# astablemultivibrator.net
KiCad netlist of a schematic drawn in EAGLE
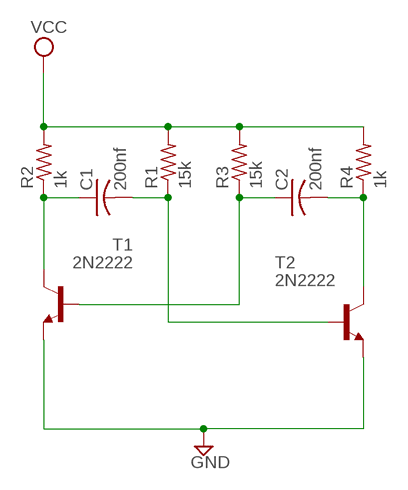
[diagram p0: schematic, sheet 1]

(export (version "E")
  (design (tool "Eeschema 10.0.6"))
  (components
    (comp (ref "C1")
      (value "200nf")
      (footprint "eagle-import:C025-030X050")
      (libsource (lib "eagle-import") (part "C-US025-030X050"))
    )
    (comp (ref "C2")
      (value "200nf")
      (footprint "eagle-import:C025-030X050")
      (libsource (lib "eagle-import") (part "C-US025-030X050"))
    )
    (comp (ref "R1")
      (value "15k")
      (footprint "eagle-import:0309_12")
      (libsource (lib "eagle-import") (part "R-US_0309/12"))
    )
    (comp (ref "R2")
      (value "1k")
      (footprint "eagle-import:0309_12")
      (libsource (lib "eagle-import") (part "R-US_0309/12"))
    )
    (comp (ref "R3")
      (value "15k")
      (footprint "eagle-import:0309_12")
      (libsource (lib "eagle-import") (part "R-US_0309/12"))
    )
    (comp (ref "R4")
      (value "1k")
      (footprint "eagle-import:0309_12")
      (libsource (lib "eagle-import") (part "R-US_0309/12"))
    )
    (comp (ref "T1")
      (value "2N2222")
      (footprint "eagle-import:TO92-EBC-OVAL")
      (libsource (lib "eagle-import") (part "2N2222"))
    )
    (comp (ref "T2")
      (value "2N2222")
      (footprint "eagle-import:TO92-EBC-OVAL")
      (libsource (lib "eagle-import") (part "2N2222"))
    )
  )
  (nets
    (net (code "1") (name "GND") (class "Default")
      (node (ref "T1") (pin "E") (pinfunction "E_E") (pintype "passive"))
      (node (ref "T2") (pin "E") (pinfunction "E_E") (pintype "passive"))
    )
    (net (code "2") (name "Net-(C1-Pad1)") (class "Default")
      (node (ref "C1") (pin "1") (pinfunction "1_1") (pintype "passive"))
      (node (ref "R2") (pin "1") (pinfunction "1_1") (pintype "passive"))
      (node (ref "T1") (pin "C") (pinfunction "C_C") (pintype "passive"))
    )
    (net (code "3") (name "Net-(C1-Pad2)") (class "Default")
      (node (ref "C1") (pin "2") (pinfunction "2_2") (pintype "passive"))
      (node (ref "R1") (pin "1") (pinfunction "1_1") (pintype "passive"))
      (node (ref "T2") (pin "B") (pinfunction "B_B") (pintype "passive"))
    )
    (net (code "4") (name "Net-(C2-Pad1)") (class "Default")
      (node (ref "C2") (pin "1") (pinfunction "1_1") (pintype "passive"))
      (node (ref "R3") (pin "1") (pinfunction "1_1") (pintype "passive"))
      (node (ref "T1") (pin "B") (pinfunction "B_B") (pintype "passive"))
    )
    (net (code "5") (name "Net-(C2-Pad2)") (class "Default")
      (node (ref "C2") (pin "2") (pinfunction "2_2") (pintype "passive"))
      (node (ref "R4") (pin "1") (pinfunction "1_1") (pintype "passive"))
      (node (ref "T2") (pin "C") (pinfunction "C_C") (pintype "passive"))
    )
    (net (code "6") (name "VCC") (class "Default")
      (node (ref "R1") (pin "2") (pinfunction "2_2") (pintype "passive"))
      (node (ref "R2") (pin "2") (pinfunction "2_2") (pintype "passive"))
      (node (ref "R3") (pin "2") (pinfunction "2_2") (pintype "passive"))
      (node (ref "R4") (pin "2") (pinfunction "2_2") (pintype "passive"))
    )
  )
)
